# Raspberry_Pi_IMU_shield_vFinal.net
KiCad netlist of a schematic drawn in EAGLE
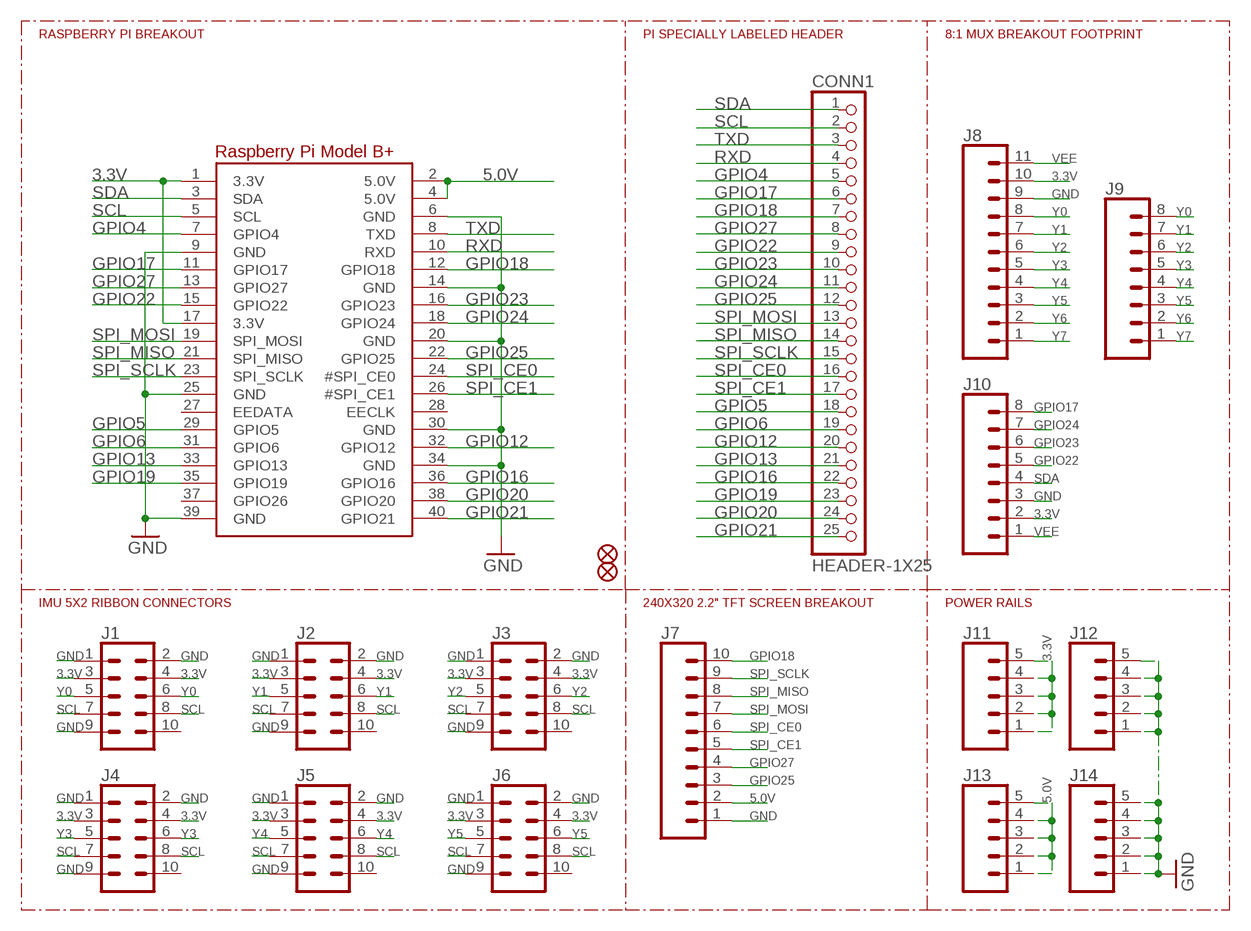
[diagram p0: schematic, sheet 1]

(export (version "E")
  (design (tool "Eeschema 10.0.6"))
  (components
    (comp (ref "CONN1")
      (value "HEADER-1X25")
      (footprint "eagle-import:1X25_ROUND_70MIL")
      (libsource (lib "eagle-import") (part "HEADER-1X25"))
    )
    (comp (ref "FID2")
      (value "FIDUCIAL\"\"")
      (footprint "eagle-import:FIDUCIAL_1MM")
      (libsource (lib "eagle-import") (part "FIDUCIAL{dblquote}{dblquote}"))
    )
    (comp (ref "FID3")
      (value "FIDUCIAL\"\"")
      (footprint "eagle-import:FIDUCIAL_1MM")
      (libsource (lib "eagle-import") (part "FIDUCIAL{dblquote}{dblquote}"))
    )
    (comp (ref "J1")
      (value "CONN_05X2SHD")
      (footprint "eagle-import:2X5-SHROUDED")
      (libsource (lib "eagle-import") (part "CONN_05X2SHD"))
    )
    (comp (ref "J2")
      (value "CONN_05X2SHD")
      (footprint "eagle-import:2X5-SHROUDED")
      (libsource (lib "eagle-import") (part "CONN_05X2SHD"))
    )
    (comp (ref "J3")
      (value "CONN_05X2SHD")
      (footprint "eagle-import:2X5-SHROUDED")
      (libsource (lib "eagle-import") (part "CONN_05X2SHD"))
    )
    (comp (ref "J4")
      (value "CONN_05X2SHD")
      (footprint "eagle-import:2X5-SHROUDED")
      (libsource (lib "eagle-import") (part "CONN_05X2SHD"))
    )
    (comp (ref "J5")
      (value "CONN_05X2SHD")
      (footprint "eagle-import:2X5-SHROUDED")
      (libsource (lib "eagle-import") (part "CONN_05X2SHD"))
    )
    (comp (ref "J6")
      (value "CONN_05X2SHD")
      (footprint "eagle-import:2X5-SHROUDED")
      (libsource (lib "eagle-import") (part "CONN_05X2SHD"))
    )
    (comp (ref "J7")
      (value "CONN_10LOCK")
      (footprint "eagle-import:1X10_LOCK")
      (libsource (lib "eagle-import") (part "CONN_10LOCK"))
    )
    (comp (ref "J8")
      (value "CONN_111X11_NO_SILK_KIT")
      (footprint "eagle-import:1X11_NO_SILK_KIT")
      (libsource (lib "eagle-import") (part "CONN_111X11_NO_SILK_KIT"))
    )
    (comp (ref "J9")
      (value "CONN_08NO_SILK_FEMALE_PTH")
      (footprint "eagle-import:1X08_NO_SILK")
      (libsource (lib "eagle-import") (part "CONN_08NO_SILK_FEMALE_PTH"))
    )
    (comp (ref "J10")
      (value "CONN_08NO_SILK_FEMALE_PTH")
      (footprint "eagle-import:1X08_NO_SILK")
      (libsource (lib "eagle-import") (part "CONN_08NO_SILK_FEMALE_PTH"))
    )
    (comp (ref "J11")
      (value "CONN_05")
      (footprint "eagle-import:1X05")
      (libsource (lib "eagle-import") (part "CONN_05"))
    )
    (comp (ref "J12")
      (value "CONN_05")
      (footprint "eagle-import:1X05")
      (libsource (lib "eagle-import") (part "CONN_05"))
    )
    (comp (ref "J13")
      (value "CONN_05")
      (footprint "eagle-import:1X05")
      (libsource (lib "eagle-import") (part "CONN_05"))
    )
    (comp (ref "J14")
      (value "CONN_05")
      (footprint "eagle-import:1X05")
      (libsource (lib "eagle-import") (part "CONN_05"))
    )
    (comp (ref "RPI1")
      (value "RASPBERRYPI_BPLUS_HATNOSLOTS")
      (footprint "eagle-import:PI_HAT_NOSLOTS")
      (libsource (lib "eagle-import") (part "RASPBERRYPI_BPLUS_HATNOSLOTS"))
    )
  )
  (nets
    (net (code "1") (name "/3.3V") (class "Default")
      (node (ref "J1") (pin "3") (pinfunction "3_3") (pintype "passive"))
      (node (ref "J1") (pin "4") (pinfunction "4_4") (pintype "passive"))
      (node (ref "J10") (pin "2") (pinfunction "2_2") (pintype "passive"))
      (node (ref "J11") (pin "1") (pinfunction "1_1") (pintype "passive"))
      (node (ref "J11") (pin "2") (pinfunction "2_2") (pintype "passive"))
      (node (ref "J11") (pin "3") (pinfunction "3_3") (pintype "passive"))
      (node (ref "J11") (pin "4") (pinfunction "4_4") (pintype "passive"))
      (node (ref "J11") (pin "5") (pinfunction "5_5") (pintype "passive"))
      (node (ref "J2") (pin "3") (pinfunction "3_3") (pintype "passive"))
      (node (ref "J2") (pin "4") (pinfunction "4_4") (pintype "passive"))
      (node (ref "J3") (pin "3") (pinfunction "3_3") (pintype "passive"))
      (node (ref "J3") (pin "4") (pinfunction "4_4") (pintype "passive"))
      (node (ref "J4") (pin "3") (pinfunction "3_3") (pintype "passive"))
      (node (ref "J4") (pin "4") (pinfunction "4_4") (pintype "passive"))
      (node (ref "J5") (pin "3") (pinfunction "3_3") (pintype "passive"))
      (node (ref "J5") (pin "4") (pinfunction "4_4") (pintype "passive"))
      (node (ref "J6") (pin "3") (pinfunction "3_3") (pintype "passive"))
      (node (ref "J6") (pin "4") (pinfunction "4_4") (pintype "passive"))
      (node (ref "J8") (pin "10") (pinfunction "10_10") (pintype "passive"))
      (node (ref "RPI1") (pin "1") (pinfunction "3.3V_1") (pintype "power_in"))
      (node (ref "RPI1") (pin "17") (pinfunction "3.3V_17") (pintype "power_in"))
    )
    (net (code "2") (name "/5.0V") (class "Default")
      (node (ref "J13") (pin "1") (pinfunction "1_1") (pintype "passive"))
      (node (ref "J13") (pin "2") (pinfunction "2_2") (pintype "passive"))
      (node (ref "J13") (pin "3") (pinfunction "3_3") (pintype "passive"))
      (node (ref "J13") (pin "4") (pinfunction "4_4") (pintype "passive"))
      (node (ref "J13") (pin "5") (pinfunction "5_5") (pintype "passive"))
      (node (ref "J7") (pin "2") (pinfunction "2_2") (pintype "passive"))
      (node (ref "RPI1") (pin "2") (pinfunction "5.0V_2") (pintype "power_in"))
      (node (ref "RPI1") (pin "4") (pinfunction "5.0V_4") (pintype "power_in"))
    )
    (net (code "3") (name "/EECLK") (class "Default")
      (node (ref "RPI1") (pin "28") (pinfunction "EECLK_28") (pintype "power_in"))
    )
    (net (code "4") (name "/GPIO4") (class "Default")
      (node (ref "CONN1") (pin "5") (pinfunction "5_5") (pintype "passive"))
      (node (ref "RPI1") (pin "7") (pinfunction "GPIO4_7") (pintype "bidirectional"))
    )
    (net (code "5") (name "/GPIO5") (class "Default")
      (node (ref "CONN1") (pin "18") (pinfunction "18_18") (pintype "passive"))
      (node (ref "RPI1") (pin "29") (pinfunction "GPIO5_29") (pintype "bidirectional"))
    )
    (net (code "6") (name "/GPIO6") (class "Default")
      (node (ref "CONN1") (pin "19") (pinfunction "19_19") (pintype "passive"))
      (node (ref "RPI1") (pin "31") (pinfunction "GPIO6_31") (pintype "power_in"))
    )
    (net (code "7") (name "/GPIO12") (class "Default")
      (node (ref "CONN1") (pin "20") (pinfunction "20_20") (pintype "passive"))
      (node (ref "RPI1") (pin "32") (pinfunction "GPIO12_32") (pintype "bidirectional"))
    )
    (net (code "8") (name "/GPIO13") (class "Default")
      (node (ref "CONN1") (pin "21") (pinfunction "21_21") (pintype "passive"))
      (node (ref "RPI1") (pin "33") (pinfunction "GPIO13_33") (pintype "bidirectional"))
    )
    (net (code "9") (name "/GPIO16") (class "Default")
      (node (ref "CONN1") (pin "22") (pinfunction "22_22") (pintype "passive"))
      (node (ref "RPI1") (pin "36") (pinfunction "GPIO16_36") (pintype "power_in"))
    )
    (net (code "10") (name "/GPIO17") (class "Default")
      (node (ref "CONN1") (pin "6") (pinfunction "6_6") (pintype "passive"))
      (node (ref "J10") (pin "8") (pinfunction "8_8") (pintype "passive"))
      (node (ref "RPI1") (pin "11") (pinfunction "GPIO17_11") (pintype "bidirectional"))
    )
    (net (code "11") (name "/GPIO18") (class "Default")
      (node (ref "CONN1") (pin "7") (pinfunction "7_7") (pintype "passive"))
      (node (ref "J7") (pin "10") (pinfunction "10_10") (pintype "passive"))
      (node (ref "RPI1") (pin "12") (pinfunction "GPIO18_12") (pintype "bidirectional"))
    )
    (net (code "12") (name "/GPIO19") (class "Default")
      (node (ref "CONN1") (pin "23") (pinfunction "23_23") (pintype "passive"))
      (node (ref "RPI1") (pin "35") (pinfunction "GPIO19_35") (pintype "bidirectional"))
    )
    (net (code "13") (name "/GPIO20") (class "Default")
      (node (ref "CONN1") (pin "24") (pinfunction "24_24") (pintype "passive"))
      (node (ref "RPI1") (pin "38") (pinfunction "GPIO20_38") (pintype "bidirectional"))
    )
    (net (code "14") (name "/GPIO21") (class "Default")
      (node (ref "CONN1") (pin "25") (pinfunction "25_25") (pintype "passive"))
      (node (ref "RPI1") (pin "40") (pinfunction "GPIO21_40") (pintype "bidirectional"))
    )
    (net (code "15") (name "/GPIO22") (class "Default")
      (node (ref "CONN1") (pin "9") (pinfunction "9_9") (pintype "passive"))
      (node (ref "J10") (pin "5") (pinfunction "5_5") (pintype "passive"))
      (node (ref "RPI1") (pin "15") (pinfunction "GPIO22_15") (pintype "bidirectional"))
    )
    (net (code "16") (name "/GPIO23") (class "Default")
      (node (ref "CONN1") (pin "10") (pinfunction "10_10") (pintype "passive"))
      (node (ref "J10") (pin "6") (pinfunction "6_6") (pintype "passive"))
      (node (ref "RPI1") (pin "16") (pinfunction "GPIO23_16") (pintype "bidirectional"))
    )
    (net (code "17") (name "/GPIO24") (class "Default")
      (node (ref "CONN1") (pin "11") (pinfunction "11_11") (pintype "passive"))
      (node (ref "J10") (pin "7") (pinfunction "7_7") (pintype "passive"))
      (node (ref "RPI1") (pin "18") (pinfunction "GPIO24_18") (pintype "bidirectional"))
    )
    (net (code "18") (name "/GPIO25") (class "Default")
      (node (ref "CONN1") (pin "12") (pinfunction "12_12") (pintype "passive"))
      (node (ref "J7") (pin "3") (pinfunction "3_3") (pintype "passive"))
      (node (ref "RPI1") (pin "22") (pinfunction "GPIO25_22") (pintype "bidirectional"))
    )
    (net (code "19") (name "/GPIO27") (class "Default")
      (node (ref "CONN1") (pin "8") (pinfunction "8_8") (pintype "passive"))
      (node (ref "J7") (pin "4") (pinfunction "4_4") (pintype "passive"))
      (node (ref "RPI1") (pin "13") (pinfunction "GPIO27_13") (pintype "bidirectional"))
    )
    (net (code "20") (name "/RXD") (class "Default")
      (node (ref "CONN1") (pin "4") (pinfunction "4_4") (pintype "passive"))
      (node (ref "RPI1") (pin "10") (pinfunction "RXD_10") (pintype "bidirectional"))
    )
    (net (code "21") (name "/SCL") (class "Default")
      (node (ref "CONN1") (pin "2") (pinfunction "2_2") (pintype "passive"))
      (node (ref "J1") (pin "7") (pinfunction "7_7") (pintype "passive"))
      (node (ref "J1") (pin "8") (pinfunction "8_8") (pintype "passive"))
      (node (ref "J2") (pin "7") (pinfunction "7_7") (pintype "passive"))
      (node (ref "J2") (pin "8") (pinfunction "8_8") (pintype "passive"))
      (node (ref "J3") (pin "7") (pinfunction "7_7") (pintype "passive"))
      (node (ref "J3") (pin "8") (pinfunction "8_8") (pintype "passive"))
      (node (ref "J4") (pin "7") (pinfunction "7_7") (pintype "passive"))
      (node (ref "J4") (pin "8") (pinfunction "8_8") (pintype "passive"))
      (node (ref "J5") (pin "7") (pinfunction "7_7") (pintype "passive"))
      (node (ref "J5") (pin "8") (pinfunction "8_8") (pintype "passive"))
      (node (ref "J6") (pin "7") (pinfunction "7_7") (pintype "passive"))
      (node (ref "J6") (pin "8") (pinfunction "8_8") (pintype "passive"))
      (node (ref "RPI1") (pin "5") (pinfunction "SCL_5") (pintype "bidirectional"))
    )
    (net (code "22") (name "/SDA") (class "Default")
      (node (ref "CONN1") (pin "1") (pinfunction "1_1") (pintype "passive"))
      (node (ref "J10") (pin "4") (pinfunction "4_4") (pintype "passive"))
      (node (ref "RPI1") (pin "3") (pinfunction "SDA_3") (pintype "bidirectional"))
    )
    (net (code "23") (name "/SPI_CE0") (class "Default")
      (node (ref "CONN1") (pin "16") (pinfunction "16_16") (pintype "passive"))
      (node (ref "J7") (pin "6") (pinfunction "6_6") (pintype "passive"))
      (node (ref "RPI1") (pin "24") (pinfunction "#SPI_CE0_24") (pintype "bidirectional"))
    )
    (net (code "24") (name "/SPI_CE1") (class "Default")
      (node (ref "CONN1") (pin "17") (pinfunction "17_17") (pintype "passive"))
      (node (ref "J7") (pin "5") (pinfunction "5_5") (pintype "passive"))
      (node (ref "RPI1") (pin "26") (pinfunction "#SPI_CE1_26") (pintype "bidirectional"))
    )
    (net (code "25") (name "/SPI_MISO") (class "Default")
      (node (ref "CONN1") (pin "14") (pinfunction "14_14") (pintype "passive"))
      (node (ref "J7") (pin "8") (pinfunction "8_8") (pintype "passive"))
      (node (ref "RPI1") (pin "21") (pinfunction "SPI_MISO_21") (pintype "bidirectional"))
    )
    (net (code "26") (name "/SPI_MOSI") (class "Default")
      (node (ref "CONN1") (pin "13") (pinfunction "13_13") (pintype "passive"))
      (node (ref "J7") (pin "7") (pinfunction "7_7") (pintype "passive"))
      (node (ref "RPI1") (pin "19") (pinfunction "SPI_MOSI_19") (pintype "bidirectional"))
    )
    (net (code "27") (name "/SPI_SCLK") (class "Default")
      (node (ref "CONN1") (pin "15") (pinfunction "15_15") (pintype "passive"))
      (node (ref "J7") (pin "9") (pinfunction "9_9") (pintype "passive"))
      (node (ref "RPI1") (pin "23") (pinfunction "SPI_SCLK_23") (pintype "bidirectional"))
    )
    (net (code "28") (name "/TXD") (class "Default")
      (node (ref "CONN1") (pin "3") (pinfunction "3_3") (pintype "passive"))
      (node (ref "RPI1") (pin "8") (pinfunction "TXD_8") (pintype "output"))
    )
    (net (code "29") (name "/VEE") (class "Default")
      (node (ref "J10") (pin "1") (pinfunction "1_1") (pintype "passive"))
      (node (ref "J8") (pin "11") (pinfunction "11_11") (pintype "passive"))
    )
    (net (code "30") (name "/Y0") (class "Default")
      (node (ref "J1") (pin "5") (pinfunction "5_5") (pintype "passive"))
      (node (ref "J1") (pin "6") (pinfunction "6_6") (pintype "passive"))
      (node (ref "J8") (pin "8") (pinfunction "8_8") (pintype "passive"))
      (node (ref "J9") (pin "8") (pinfunction "8_8") (pintype "passive"))
    )
    (net (code "31") (name "/Y1") (class "Default")
      (node (ref "J2") (pin "5") (pinfunction "5_5") (pintype "passive"))
      (node (ref "J2") (pin "6") (pinfunction "6_6") (pintype "passive"))
      (node (ref "J8") (pin "7") (pinfunction "7_7") (pintype "passive"))
      (node (ref "J9") (pin "7") (pinfunction "7_7") (pintype "passive"))
    )
    (net (code "32") (name "/Y2") (class "Default")
      (node (ref "J3") (pin "5") (pinfunction "5_5") (pintype "passive"))
      (node (ref "J3") (pin "6") (pinfunction "6_6") (pintype "passive"))
      (node (ref "J8") (pin "6") (pinfunction "6_6") (pintype "passive"))
      (node (ref "J9") (pin "6") (pinfunction "6_6") (pintype "passive"))
    )
    (net (code "33") (name "/Y3") (class "Default")
      (node (ref "J4") (pin "5") (pinfunction "5_5") (pintype "passive"))
      (node (ref "J4") (pin "6") (pinfunction "6_6") (pintype "passive"))
      (node (ref "J8") (pin "5") (pinfunction "5_5") (pintype "passive"))
      (node (ref "J9") (pin "5") (pinfunction "5_5") (pintype "passive"))
    )
    (net (code "34") (name "/Y4") (class "Default")
      (node (ref "J5") (pin "5") (pinfunction "5_5") (pintype "passive"))
      (node (ref "J5") (pin "6") (pinfunction "6_6") (pintype "passive"))
      (node (ref "J8") (pin "4") (pinfunction "4_4") (pintype "passive"))
      (node (ref "J9") (pin "4") (pinfunction "4_4") (pintype "passive"))
    )
    (net (code "35") (name "/Y5") (class "Default")
      (node (ref "J6") (pin "5") (pinfunction "5_5") (pintype "passive"))
      (node (ref "J6") (pin "6") (pinfunction "6_6") (pintype "passive"))
      (node (ref "J8") (pin "3") (pinfunction "3_3") (pintype "passive"))
      (node (ref "J9") (pin "3") (pinfunction "3_3") (pintype "passive"))
    )
    (net (code "36") (name "/Y6") (class "Default")
      (node (ref "J8") (pin "2") (pinfunction "2_2") (pintype "passive"))
      (node (ref "J9") (pin "2") (pinfunction "2_2") (pintype "passive"))
    )
    (net (code "37") (name "/Y7") (class "Default")
      (node (ref "J8") (pin "1") (pinfunction "1_1") (pintype "passive"))
      (node (ref "J9") (pin "1") (pinfunction "1_1") (pintype "passive"))
    )
    (net (code "38") (name "GND") (class "Default")
      (node (ref "J1") (pin "1") (pinfunction "1_1") (pintype "passive"))
      (node (ref "J1") (pin "2") (pinfunction "2_2") (pintype "passive"))
      (node (ref "J1") (pin "9") (pinfunction "9_9") (pintype "passive"))
      (node (ref "J10") (pin "3") (pinfunction "3_3") (pintype "passive"))
      (node (ref "J12") (pin "1") (pinfunction "1_1") (pintype "passive"))
      (node (ref "J12") (pin "2") (pinfunction "2_2") (pintype "passive"))
      (node (ref "J12") (pin "3") (pinfunction "3_3") (pintype "passive"))
      (node (ref "J12") (pin "4") (pinfunction "4_4") (pintype "passive"))
      (node (ref "J12") (pin "5") (pinfunction "5_5") (pintype "passive"))
      (node (ref "J14") (pin "1") (pinfunction "1_1") (pintype "passive"))
      (node (ref "J14") (pin "2") (pinfunction "2_2") (pintype "passive"))
      (node (ref "J14") (pin "3") (pinfunction "3_3") (pintype "passive"))
      (node (ref "J14") (pin "4") (pinfunction "4_4") (pintype "passive"))
      (node (ref "J14") (pin "5") (pinfunction "5_5") (pintype "passive"))
      (node (ref "J2") (pin "1") (pinfunction "1_1") (pintype "passive"))
      (node (ref "J2") (pin "2") (pinfunction "2_2") (pintype "passive"))
      (node (ref "J2") (pin "9") (pinfunction "9_9") (pintype "passive"))
      (node (ref "J3") (pin "1") (pinfunction "1_1") (pintype "passive"))
      (node (ref "J3") (pin "2") (pinfunction "2_2") (pintype "passive"))
      (node (ref "J3") (pin "9") (pinfunction "9_9") (pintype "passive"))
      (node (ref "J4") (pin "1") (pinfunction "1_1") (pintype "passive"))
      (node (ref "J4") (pin "2") (pinfunction "2_2") (pintype "passive"))
      (node (ref "J4") (pin "9") (pinfunction "9_9") (pintype "passive"))
      (node (ref "J5") (pin "1") (pinfunction "1_1") (pintype "passive"))
      (node (ref "J5") (pin "2") (pinfunction "2_2") (pintype "passive"))
      (node (ref "J5") (pin "9") (pinfunction "9_9") (pintype "passive"))
      (node (ref "J6") (pin "1") (pinfunction "1_1") (pintype "passive"))
      (node (ref "J6") (pin "2") (pinfunction "2_2") (pintype "passive"))
      (node (ref "J6") (pin "9") (pinfunction "9_9") (pintype "passive"))
      (node (ref "J7") (pin "1") (pinfunction "1_1") (pintype "passive"))
      (node (ref "J8") (pin "9") (pinfunction "9_9") (pintype "passive"))
      (node (ref "RPI1") (pin "14") (pinfunction "GND_14") (pintype "power_in"))
      (node (ref "RPI1") (pin "20") (pinfunction "GND_20") (pintype "power_in"))
      (node (ref "RPI1") (pin "25") (pinfunction "GND_25") (pintype "power_in"))
      (node (ref "RPI1") (pin "30") (pinfunction "GND_30") (pintype "bidirectional"))
      (node (ref "RPI1") (pin "34") (pinfunction "GND_34") (pintype "bidirectional"))
      (node (ref "RPI1") (pin "39") (pinfunction "GND_39") (pintype "power_in"))
      (node (ref "RPI1") (pin "6") (pinfunction "GND_6") (pintype "power_in"))
      (node (ref "RPI1") (pin "9") (pinfunction "GND_9") (pintype "power_in"))
    )
    (net (code "39") (name "unconnected-(J1-Pad10)") (class "Default")
      (node (ref "J1") (pin "10") (pinfunction "10_10") (pintype "passive"))
    )
    (net (code "40") (name "unconnected-(J2-Pad10)") (class "Default")
      (node (ref "J2") (pin "10") (pinfunction "10_10") (pintype "passive"))
    )
    (net (code "41") (name "unconnected-(J3-Pad10)") (class "Default")
      (node (ref "J3") (pin "10") (pinfunction "10_10") (pintype "passive"))
    )
    (net (code "42") (name "unconnected-(J4-Pad10)") (class "Default")
      (node (ref "J4") (pin "10") (pinfunction "10_10") (pintype "passive"))
    )
    (net (code "43") (name "unconnected-(J5-Pad10)") (class "Default")
      (node (ref "J5") (pin "10") (pinfunction "10_10") (pintype "passive"))
    )
    (net (code "44") (name "unconnected-(J6-Pad10)") (class "Default")
      (node (ref "J6") (pin "10") (pinfunction "10_10") (pintype "passive"))
    )
    (net (code "45") (name "unconnected-(RPI1-EEDATA-Pad27)") (class "Default")
      (node (ref "RPI1") (pin "27") (pinfunction "EEDATA_27") (pintype "bidirectional"))
    )
    (net (code "46") (name "unconnected-(RPI1-GPIO26-Pad37)") (class "Default")
      (node (ref "RPI1") (pin "37") (pinfunction "GPIO26_37") (pintype "bidirectional"))
    )
  )
)
